# timer555.net
KiCad netlist of a schematic drawn in EAGLE
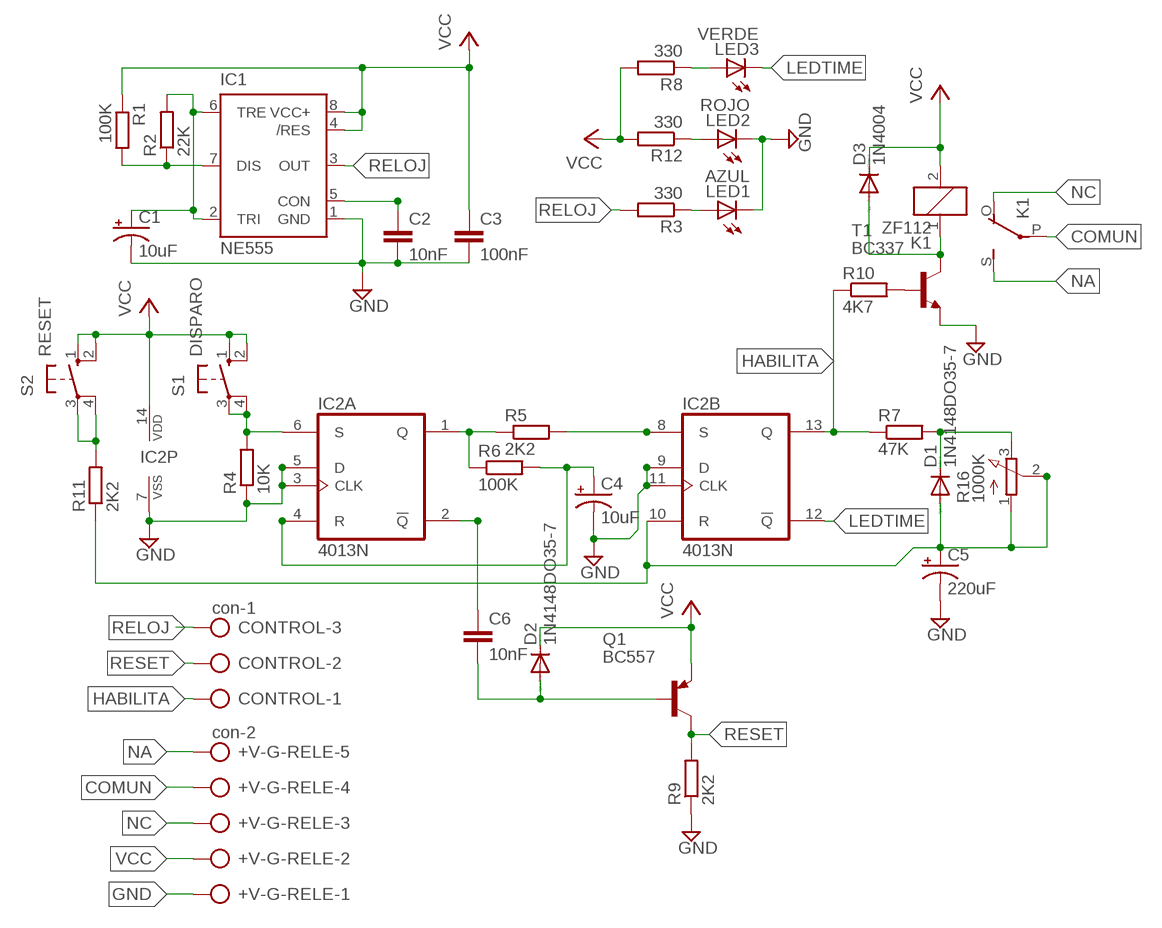
[diagram p0: schematic, sheet 1]

(export (version "E")
  (design (tool "Eeschema 10.0.6"))
  (components
    (comp (ref "+V-G-RELE")
      (value "con-2")
      (footprint "eagle-import:AK500_5")
      (libsource (lib "eagle-import") (part "AK500/5"))
    )
    (comp (ref "C1")
      (value "10uF")
      (footprint "eagle-import:E2,5-5")
      (libsource (lib "eagle-import") (part "CPOL-USE2.5-5"))
    )
    (comp (ref "C2")
      (value "10nF")
      (footprint "eagle-import:C050-025X075")
      (libsource (lib "eagle-import") (part "C-EU050-025X075"))
    )
    (comp (ref "C3")
      (value "100nF")
      (footprint "eagle-import:C050-025X075")
      (libsource (lib "eagle-import") (part "C-EU050-025X075"))
    )
    (comp (ref "C4")
      (value "10uF")
      (footprint "eagle-import:E2,5-5")
      (libsource (lib "eagle-import") (part "CPOL-USE2.5-5"))
    )
    (comp (ref "C5")
      (value "220uF")
      (footprint "eagle-import:E3,5-8")
      (libsource (lib "eagle-import") (part "CPOL-USE3.5-8"))
    )
    (comp (ref "C6")
      (value "10nF")
      (footprint "eagle-import:C050-025X075")
      (libsource (lib "eagle-import") (part "C-EU050-025X075"))
    )
    (comp (ref "CONTROL")
      (value "con-1")
      (footprint "eagle-import:AK500_3")
      (libsource (lib "eagle-import") (part "AK500/3"))
    )
    (comp (ref "D1")
      (value "1N4148DO35-7")
      (footprint "eagle-import:DO35-7")
      (libsource (lib "eagle-import") (part "1N4148DO35-7"))
    )
    (comp (ref "D2")
      (value "1N4148DO35-7")
      (footprint "eagle-import:DO35-7")
      (libsource (lib "eagle-import") (part "1N4148DO35-7"))
    )
    (comp (ref "D3")
      (value "1N4004")
      (footprint "eagle-import:DO41-10")
      (libsource (lib "eagle-import") (part "1N4004"))
    )
    (comp (ref "IC1")
      (value "NE555")
      (footprint "eagle-import:DIL-08")
      (fields (field (name "MF") "Arrow Electronics") (field (name "MPN") "NE555N"))
      (libsource (lib "eagle-import") (part "NE555"))
    )
    (comp (ref "IC2")
      (value "4013N")
      (footprint "eagle-import:DIL14")
      (libsource (lib "eagle-import") (part "4013N"))
    )
    (comp (ref "K1")
      (value "ZF112")
      (footprint "eagle-import:ZF112")
      (libsource (lib "eagle-import") (part "ZF112"))
    )
    (comp (ref "LED1")
      (value "AZUL")
      (footprint "eagle-import:LED3MM")
      (libsource (lib "eagle-import") (part "LED3MM"))
    )
    (comp (ref "LED2")
      (value "ROJO")
      (footprint "eagle-import:LED3MM")
      (libsource (lib "eagle-import") (part "LED3MM"))
    )
    (comp (ref "LED3")
      (value "VERDE")
      (footprint "eagle-import:LED3MM")
      (libsource (lib "eagle-import") (part "LED3MM"))
    )
    (comp (ref "Q1")
      (value "BC557")
      (footprint "eagle-import:TO92-EBC")
      (libsource (lib "eagle-import") (part "BC557"))
    )
    (comp (ref "R1")
      (value "100K")
      (footprint "eagle-import:0207_7")
      (libsource (lib "eagle-import") (part "R-EU_0207/7"))
    )
    (comp (ref "R2")
      (value "22K")
      (footprint "eagle-import:0207_7")
      (libsource (lib "eagle-import") (part "R-EU_0207/7"))
    )
    (comp (ref "R3")
      (value "330")
      (footprint "eagle-import:0207_7")
      (libsource (lib "eagle-import") (part "R-EU_0207/7"))
    )
    (comp (ref "R4")
      (value "10K")
      (footprint "eagle-import:0207_7")
      (libsource (lib "eagle-import") (part "R-EU_0207/7"))
    )
    (comp (ref "R5")
      (value "2K2")
      (footprint "eagle-import:0207_7")
      (libsource (lib "eagle-import") (part "R-EU_0207/7"))
    )
    (comp (ref "R6")
      (value "100K")
      (footprint "eagle-import:0207_7")
      (libsource (lib "eagle-import") (part "R-EU_0207/7"))
    )
    (comp (ref "R7")
      (value "47K")
      (footprint "eagle-import:0207_7")
      (libsource (lib "eagle-import") (part "R-EU_0207/7"))
    )
    (comp (ref "R8")
      (value "330")
      (footprint "eagle-import:0207_7")
      (libsource (lib "eagle-import") (part "R-EU_0207/7"))
    )
    (comp (ref "R9")
      (value "2K2")
      (footprint "eagle-import:0207_7")
      (libsource (lib "eagle-import") (part "R-EU_0207/7"))
    )
    (comp (ref "R10")
      (value "4K7")
      (footprint "eagle-import:0207_7")
      (libsource (lib "eagle-import") (part "R-EU_0207/7"))
    )
    (comp (ref "R11")
      (value "2K2")
      (footprint "eagle-import:0207_7")
      (libsource (lib "eagle-import") (part "R-EU_0207/7"))
    )
    (comp (ref "R12")
      (value "330")
      (footprint "eagle-import:0207_7")
      (libsource (lib "eagle-import") (part "R-EU_0207/7"))
    )
    (comp (ref "R16")
      (value "1000K")
      (footprint "eagle-import:3RP_1610N")
      (libsource (lib "eagle-import") (part "3RP/1610N"))
    )
    (comp (ref "S1")
      (value "DISPARO")
      (footprint "eagle-import:B3F-10XX")
      (fields (field (name "MPN") "B3F-1000"))
      (libsource (lib "eagle-import") (part "10-XX"))
    )
    (comp (ref "S2")
      (value "RESET")
      (footprint "eagle-import:B3F-10XX")
      (fields (field (name "MPN") "B3F-1000"))
      (libsource (lib "eagle-import") (part "10-XX"))
    )
    (comp (ref "T1")
      (value "BC337")
      (footprint "eagle-import:TO92")
      (libsource (lib "eagle-import") (part "BC337"))
    )
  )
  (nets
    (net (code "1") (name "COMUN") (class "Default")
      (node (ref "+V-G-RELE") (pin "4") (pinfunction "KL_4") (pintype "passive"))
      (node (ref "K1") (pin "P") (pinfunction "P_P") (pintype "passive"))
    )
    (net (code "2") (name "GND") (class "Default")
      (node (ref "+V-G-RELE") (pin "1") (pinfunction "KL_1") (pintype "passive"))
      (node (ref "C1") (pin "-") (pinfunction "-_-") (pintype "passive"))
      (node (ref "C2") (pin "2") (pinfunction "2_2") (pintype "passive"))
      (node (ref "C3") (pin "2") (pinfunction "2_2") (pintype "passive"))
      (node (ref "C4") (pin "-") (pinfunction "-_-") (pintype "passive"))
      (node (ref "C5") (pin "-") (pinfunction "-_-") (pintype "passive"))
      (node (ref "IC1") (pin "1") (pinfunction "GND_1") (pintype "power_in"))
      (node (ref "IC2") (pin "11") (pinfunction "CLK_11") (pintype "input"))
      (node (ref "IC2") (pin "3") (pinfunction "CLK_3") (pintype "input"))
      (node (ref "IC2") (pin "5") (pinfunction "D_5") (pintype "input"))
      (node (ref "IC2") (pin "7") (pinfunction "VSS_7") (pintype "power_in"))
      (node (ref "IC2") (pin "9") (pinfunction "D_9") (pintype "input"))
      (node (ref "LED1") (pin "K") (pinfunction "C_K") (pintype "passive"))
      (node (ref "LED2") (pin "K") (pinfunction "C_K") (pintype "passive"))
      (node (ref "R4") (pin "1") (pinfunction "1_1") (pintype "passive"))
      (node (ref "R9") (pin "1") (pinfunction "1_1") (pintype "passive"))
      (node (ref "T1") (pin "1") (pinfunction "E_1") (pintype "passive"))
    )
    (net (code "3") (name "HABILITA") (class "Default")
      (node (ref "CONTROL") (pin "1") (pinfunction "KL_1") (pintype "passive"))
      (node (ref "IC2") (pin "13") (pinfunction "Q_13") (pintype "output"))
      (node (ref "R10") (pin "1") (pinfunction "1_1") (pintype "passive"))
      (node (ref "R7") (pin "1") (pinfunction "1_1") (pintype "passive"))
    )
    (net (code "4") (name "LEDTIME") (class "Default")
      (node (ref "IC2") (pin "12") (pinfunction "~{Q}_12") (pintype "output"))
      (node (ref "LED3") (pin "K") (pinfunction "C_K") (pintype "passive"))
    )
    (net (code "5") (name "NA") (class "Default")
      (node (ref "+V-G-RELE") (pin "5") (pinfunction "KL_5") (pintype "passive"))
      (node (ref "K1") (pin "S") (pinfunction "S_S") (pintype "passive"))
    )
    (net (code "6") (name "NC") (class "Default")
      (node (ref "+V-G-RELE") (pin "3") (pinfunction "KL_3") (pintype "passive"))
      (node (ref "K1") (pin "O") (pinfunction "O_O") (pintype "passive"))
    )
    (net (code "7") (name "Net-(C6-Pad2)") (class "Default")
      (node (ref "C6") (pin "2") (pinfunction "2_2") (pintype "passive"))
      (node (ref "D2") (pin "A") (pinfunction "A_A") (pintype "passive"))
      (node (ref "Q1") (pin "B") (pinfunction "B_B") (pintype "passive"))
    )
    (net (code "8") (name "Net-(IC1-CON)") (class "Default")
      (node (ref "C2") (pin "1") (pinfunction "1_1") (pintype "passive"))
      (node (ref "IC1") (pin "5") (pinfunction "CON_5") (pintype "input"))
    )
    (net (code "9") (name "Net-(IC1-DIS)") (class "Default")
      (node (ref "IC1") (pin "7") (pinfunction "DIS_7") (pintype "input"))
      (node (ref "R1") (pin "2") (pinfunction "2_2") (pintype "passive"))
      (node (ref "R2") (pin "1") (pinfunction "1_1") (pintype "passive"))
    )
    (net (code "10") (name "Net-(IC1-TRE)") (class "Default")
      (node (ref "C1") (pin "+") (pinfunction "+_+") (pintype "passive"))
      (node (ref "IC1") (pin "2") (pinfunction "TRI_2") (pintype "input"))
      (node (ref "IC1") (pin "6") (pinfunction "TRE_6") (pintype "input"))
      (node (ref "R2") (pin "2") (pinfunction "2_2") (pintype "passive"))
    )
    (net (code "11") (name "Net-(IC2A-Q)") (class "Default")
      (node (ref "IC2") (pin "1") (pinfunction "Q_1") (pintype "output"))
      (node (ref "R5") (pin "1") (pinfunction "1_1") (pintype "passive"))
      (node (ref "R6") (pin "1") (pinfunction "1_1") (pintype "passive"))
    )
    (net (code "12") (name "Net-(IC2A-R)") (class "Default")
      (node (ref "C4") (pin "+") (pinfunction "+_+") (pintype "passive"))
      (node (ref "IC2") (pin "4") (pinfunction "R_4") (pintype "input"))
      (node (ref "R6") (pin "2") (pinfunction "2_2") (pintype "passive"))
    )
    (net (code "13") (name "Net-(IC2A-S)") (class "Default")
      (node (ref "IC2") (pin "6") (pinfunction "S_6") (pintype "input"))
      (node (ref "R4") (pin "2") (pinfunction "2_2") (pintype "passive"))
      (node (ref "S1") (pin "3") (pinfunction "P_3") (pintype "passive"))
      (node (ref "S1") (pin "4") (pinfunction "P1_4") (pintype "passive"))
    )
    (net (code "14") (name "Net-(IC2A-~{Q})") (class "Default")
      (node (ref "C6") (pin "1") (pinfunction "1_1") (pintype "passive"))
      (node (ref "IC2") (pin "2") (pinfunction "~{Q}_2") (pintype "output"))
    )
    (net (code "15") (name "Net-(IC2B-R)") (class "Default")
      (node (ref "C5") (pin "+") (pinfunction "+_+") (pintype "passive"))
      (node (ref "D1") (pin "A") (pinfunction "A_A") (pintype "passive"))
      (node (ref "IC2") (pin "10") (pinfunction "R_10") (pintype "input"))
      (node (ref "R11") (pin "1") (pinfunction "1_1") (pintype "passive"))
      (node (ref "R16") (pin "1") (pinfunction "A_1") (pintype "passive"))
      (node (ref "R16") (pin "2") (pinfunction "S_2") (pintype "passive"))
    )
    (net (code "16") (name "Net-(IC2B-S)") (class "Default")
      (node (ref "IC2") (pin "8") (pinfunction "S_8") (pintype "input"))
      (node (ref "R5") (pin "2") (pinfunction "2_2") (pintype "passive"))
    )
    (net (code "17") (name "Net-(LED1-PadA)") (class "Default")
      (node (ref "LED1") (pin "A") (pinfunction "A_A") (pintype "passive"))
      (node (ref "R3") (pin "1") (pinfunction "1_1") (pintype "passive"))
    )
    (net (code "18") (name "Net-(LED2-PadA)") (class "Default")
      (node (ref "LED2") (pin "A") (pinfunction "A_A") (pintype "passive"))
      (node (ref "R12") (pin "1") (pinfunction "1_1") (pintype "passive"))
    )
    (net (code "19") (name "Net-(LED3-PadA)") (class "Default")
      (node (ref "LED3") (pin "A") (pinfunction "A_A") (pintype "passive"))
      (node (ref "R8") (pin "1") (pinfunction "1_1") (pintype "passive"))
    )
    (net (code "20") (name "Net-(R16-E)") (class "Default")
      (node (ref "D1") (pin "C") (pinfunction "C_C") (pintype "passive"))
      (node (ref "R16") (pin "3") (pinfunction "E_3") (pintype "passive"))
      (node (ref "R7") (pin "2") (pinfunction "2_2") (pintype "passive"))
    )
    (net (code "21") (name "Net-(S2-P)") (class "Default")
      (node (ref "R11") (pin "2") (pinfunction "2_2") (pintype "passive"))
      (node (ref "S2") (pin "3") (pinfunction "P_3") (pintype "passive"))
      (node (ref "S2") (pin "4") (pinfunction "P1_4") (pintype "passive"))
    )
    (net (code "22") (name "Net-(T1-B)") (class "Default")
      (node (ref "R10") (pin "2") (pinfunction "2_2") (pintype "passive"))
      (node (ref "T1") (pin "2") (pinfunction "B_2") (pintype "passive"))
    )
    (net (code "23") (name "Net-(T1-C)") (class "Default")
      (node (ref "D3") (pin "A") (pinfunction "A_A") (pintype "passive"))
      (node (ref "K1") (pin "1") (pinfunction "1_1") (pintype "passive"))
      (node (ref "T1") (pin "3") (pinfunction "C_3") (pintype "passive"))
    )
    (net (code "24") (name "RELOJ") (class "Default")
      (node (ref "CONTROL") (pin "3") (pinfunction "KL_3") (pintype "passive"))
      (node (ref "IC1") (pin "3") (pinfunction "OUT_3") (pintype "output"))
      (node (ref "R3") (pin "2") (pinfunction "2_2") (pintype "passive"))
    )
    (net (code "25") (name "RESET") (class "Default")
      (node (ref "CONTROL") (pin "2") (pinfunction "KL_2") (pintype "passive"))
      (node (ref "Q1") (pin "C") (pinfunction "C_C") (pintype "passive"))
      (node (ref "R9") (pin "2") (pinfunction "2_2") (pintype "passive"))
    )
    (net (code "26") (name "VCC") (class "Default")
      (node (ref "+V-G-RELE") (pin "2") (pinfunction "KL_2") (pintype "passive"))
      (node (ref "C3") (pin "1") (pinfunction "1_1") (pintype "passive"))
      (node (ref "D2") (pin "C") (pinfunction "C_C") (pintype "passive"))
      (node (ref "D3") (pin "C") (pinfunction "C_C") (pintype "passive"))
      (node (ref "IC1") (pin "4") (pinfunction "/RES_4") (pintype "input"))
      (node (ref "IC1") (pin "8") (pinfunction "VCC+_8") (pintype "power_in"))
      (node (ref "IC2") (pin "14") (pinfunction "VDD_14") (pintype "power_in"))
      (node (ref "K1") (pin "2") (pinfunction "2_2") (pintype "passive"))
      (node (ref "Q1") (pin "E") (pinfunction "E_E") (pintype "passive"))
      (node (ref "R1") (pin "1") (pinfunction "1_1") (pintype "passive"))
      (node (ref "R12") (pin "2") (pinfunction "2_2") (pintype "passive"))
      (node (ref "R8") (pin "2") (pinfunction "2_2") (pintype "passive"))
      (node (ref "S1") (pin "1") (pinfunction "S_1") (pintype "passive"))
      (node (ref "S1") (pin "2") (pinfunction "S1_2") (pintype "passive"))
      (node (ref "S2") (pin "1") (pinfunction "S_1") (pintype "passive"))
      (node (ref "S2") (pin "2") (pinfunction "S1_2") (pintype "passive"))
    )
  )
)
